# Panel_10_100_Pasive_Schematic.net
KiCad netlist of a schematic drawn in Altium Designer
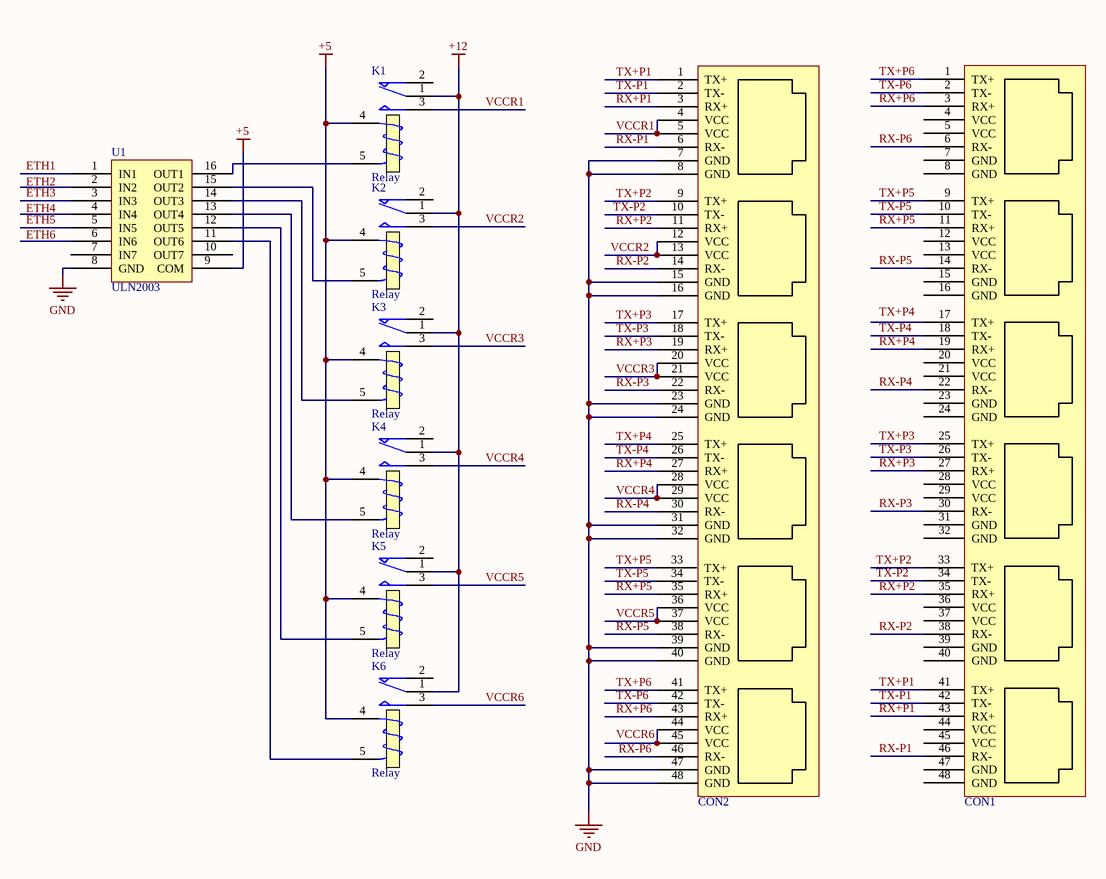
[diagram p0: Panel_10_100_Pasive_Schematic.SchDoc]

(export (version "E")
  (design (tool "Eeschema 10.0.6"))
  (components
    (comp (ref "CON1")
      (value "RJ45-w57-6")
      (footprint "RJ45-W57-6")
      (libsource (lib "Schlib1") (part "RJ45-w57-6"))
    )
    (comp (ref "CON2")
      (value "RJ45-w57-6")
      (footprint "RJ45-W57-6")
      (libsource (lib "Schlib1") (part "RJ45-w57-6"))
    )
    (comp (ref "K1")
      (value "Relay")
      (footprint "Relay 15.40x12.10x13.10")
      (description "SPDT Relay")
      (fields (field (name "DESIGNER") "Eng. Saeid Jorablo"))
      (libsource (lib "Electrovolt Lib") (part "Relay"))
    )
    (comp (ref "K2")
      (value "Relay")
      (footprint "Relay 15.40x12.10x13.10")
      (description "SPDT Relay")
      (fields (field (name "DESIGNER") "Eng. Saeid Jorablo"))
      (libsource (lib "Electrovolt Lib") (part "Relay"))
    )
    (comp (ref "K3")
      (value "Relay")
      (footprint "Relay 15.40x12.10x13.10")
      (description "SPDT Relay")
      (fields (field (name "DESIGNER") "Eng. Saeid Jorablo"))
      (libsource (lib "Electrovolt Lib") (part "Relay"))
    )
    (comp (ref "K4")
      (value "Relay")
      (footprint "Relay 15.40x12.10x13.10")
      (description "SPDT Relay")
      (fields (field (name "DESIGNER") "Eng. Saeid Jorablo"))
      (libsource (lib "Electrovolt Lib") (part "Relay"))
    )
    (comp (ref "K5")
      (value "Relay")
      (footprint "Relay 15.40x12.10x13.10")
      (description "SPDT Relay")
      (fields (field (name "DESIGNER") "Eng. Saeid Jorablo"))
      (libsource (lib "Electrovolt Lib") (part "Relay"))
    )
    (comp (ref "K6")
      (value "Relay")
      (footprint "Relay 15.40x12.10x13.10")
      (description "SPDT Relay")
      (fields (field (name "DESIGNER") "Eng. Saeid Jorablo"))
      (libsource (lib "Electrovolt Lib") (part "Relay"))
    )
    (comp (ref "U1") (value "ULN2003") (footprint "SOCI16") (libsource (lib "Schlib1") (part "ULN2003")))
  )
  (nets
    (net (code "1") (name "+5") (class "Default")
      (node (ref "K1") (pin "4") (pinfunction "T1_4") (pintype "passive"))
      (node (ref "K2") (pin "4") (pinfunction "T1_4") (pintype "passive"))
      (node (ref "K3") (pin "4") (pinfunction "T1_4") (pintype "passive"))
      (node (ref "K4") (pin "4") (pinfunction "T1_4") (pintype "passive"))
      (node (ref "K5") (pin "4") (pinfunction "T1_4") (pintype "passive"))
      (node (ref "K6") (pin "4") (pinfunction "T1_4") (pintype "passive"))
      (node (ref "U1") (pin "9") (pinfunction "COM_9") (pintype "passive"))
    )
    (net (code "2") (name "+12") (class "Default")
      (node (ref "K1") (pin "1") (pinfunction "COM_1") (pintype "passive"))
      (node (ref "K2") (pin "1") (pinfunction "COM_1") (pintype "passive"))
      (node (ref "K3") (pin "1") (pinfunction "COM_1") (pintype "passive"))
      (node (ref "K4") (pin "1") (pinfunction "COM_1") (pintype "passive"))
      (node (ref "K5") (pin "1") (pinfunction "COM_1") (pintype "passive"))
      (node (ref "K6") (pin "1") (pinfunction "COM_1") (pintype "passive"))
    )
    (net (code "3") (name "/ETH1") (class "Default")
      (node (ref "U1") (pin "1") (pinfunction "IN1_1") (pintype "passive"))
    )
    (net (code "5") (name "/ETH3") (class "Default")
      (node (ref "U1") (pin "3") (pinfunction "IN3_3") (pintype "passive"))
    )
    (net (code "7") (name "/ETH5") (class "Default")
      (node (ref "U1") (pin "5") (pinfunction "IN5_5") (pintype "passive"))
    )
    (net (code "9") (name "/RX+P1") (class "Default")
      (node (ref "CON1") (pin "43") (pinfunction "RX+_43") (pintype "passive"))
      (node (ref "CON2") (pin "3") (pinfunction "RX+_3") (pintype "passive"))
    )
    (net (code "10") (name "/RX+P2") (class "Default")
      (node (ref "CON1") (pin "35") (pinfunction "RX+_35") (pintype "passive"))
      (node (ref "CON2") (pin "11") (pinfunction "RX+_11") (pintype "passive"))
    )
    (net (code "11") (name "/RX+P3") (class "Default")
      (node (ref "CON1") (pin "27") (pinfunction "RX+_27") (pintype "passive"))
      (node (ref "CON2") (pin "19") (pinfunction "RX+_19") (pintype "passive"))
    )
    (net (code "12") (name "/RX+P4") (class "Default")
      (node (ref "CON1") (pin "19") (pinfunction "RX+_19") (pintype "passive"))
      (node (ref "CON2") (pin "27") (pinfunction "RX+_27") (pintype "passive"))
    )
    (net (code "13") (name "/RX+P5") (class "Default")
      (node (ref "CON1") (pin "11") (pinfunction "RX+_11") (pintype "passive"))
      (node (ref "CON2") (pin "35") (pinfunction "RX+_35") (pintype "passive"))
    )
    (net (code "14") (name "/RX+P6") (class "Default")
      (node (ref "CON1") (pin "3") (pinfunction "RX+_3") (pintype "passive"))
      (node (ref "CON2") (pin "43") (pinfunction "RX+_43") (pintype "passive"))
    )
    (net (code "15") (name "/RX-P1") (class "Default")
      (node (ref "CON1") (pin "46") (pinfunction "RX-_46") (pintype "passive"))
      (node (ref "CON2") (pin "6") (pinfunction "RX-_6") (pintype "passive"))
    )
    (net (code "16") (name "/RX-P2") (class "Default")
      (node (ref "CON1") (pin "38") (pinfunction "RX-_38") (pintype "passive"))
      (node (ref "CON2") (pin "14") (pinfunction "RX-_14") (pintype "passive"))
    )
    (net (code "17") (name "/RX-P3") (class "Default")
      (node (ref "CON1") (pin "30") (pinfunction "RX-_30") (pintype "passive"))
      (node (ref "CON2") (pin "22") (pinfunction "RX-_22") (pintype "passive"))
    )
    (net (code "18") (name "/RX-P4") (class "Default")
      (node (ref "CON1") (pin "22") (pinfunction "RX-_22") (pintype "passive"))
      (node (ref "CON2") (pin "30") (pinfunction "RX-_30") (pintype "passive"))
    )
    (net (code "19") (name "/RX-P5") (class "Default")
      (node (ref "CON1") (pin "14") (pinfunction "RX-_14") (pintype "passive"))
      (node (ref "CON2") (pin "38") (pinfunction "RX-_38") (pintype "passive"))
    )
    (net (code "20") (name "/RX-P6") (class "Default")
      (node (ref "CON1") (pin "6") (pinfunction "RX-_6") (pintype "passive"))
      (node (ref "CON2") (pin "46") (pinfunction "RX-_46") (pintype "passive"))
    )
    (net (code "21") (name "/TX+P1") (class "Default")
      (node (ref "CON1") (pin "41") (pinfunction "TX+_41") (pintype "passive"))
      (node (ref "CON2") (pin "1") (pinfunction "TX+_1") (pintype "passive"))
    )
    (net (code "22") (name "/TX+P2") (class "Default")
      (node (ref "CON1") (pin "33") (pinfunction "TX+_33") (pintype "passive"))
      (node (ref "CON2") (pin "9") (pinfunction "TX+_9") (pintype "passive"))
    )
    (net (code "23") (name "/TX+P3") (class "Default")
      (node (ref "CON1") (pin "25") (pinfunction "TX+_25") (pintype "passive"))
      (node (ref "CON2") (pin "17") (pinfunction "TX+_17") (pintype "passive"))
    )
    (net (code "24") (name "/TX+P4") (class "Default")
      (node (ref "CON2") (pin "25") (pinfunction "TX+_25") (pintype "passive"))
    )
    (net (code "25") (name "/TX+P5") (class "Default")
      (node (ref "CON1") (pin "9") (pinfunction "TX+_9") (pintype "passive"))
      (node (ref "CON2") (pin "33") (pinfunction "TX+_33") (pintype "passive"))
    )
    (net (code "26") (name "/TX+P6") (class "Default")
      (node (ref "CON1") (pin "1") (pinfunction "TX+_1") (pintype "passive"))
      (node (ref "CON2") (pin "41") (pinfunction "TX+_41") (pintype "passive"))
    )
    (net (code "27") (name "/TX-P1") (class "Default")
      (node (ref "CON1") (pin "42") (pinfunction "TX-_42") (pintype "passive"))
      (node (ref "CON2") (pin "2") (pinfunction "TX-_2") (pintype "passive"))
    )
    (net (code "28") (name "/TX-P2") (class "Default")
      (node (ref "CON1") (pin "34") (pinfunction "TX-_34") (pintype "passive"))
      (node (ref "CON2") (pin "10") (pinfunction "TX-_10") (pintype "passive"))
    )
    (net (code "29") (name "/TX-P3") (class "Default")
      (node (ref "CON1") (pin "26") (pinfunction "TX-_26") (pintype "passive"))
      (node (ref "CON2") (pin "18") (pinfunction "TX-_18") (pintype "passive"))
    )
    (net (code "30") (name "/TX-P4") (class "Default")
      (node (ref "CON1") (pin "18") (pinfunction "TX-_18") (pintype "passive"))
      (node (ref "CON2") (pin "26") (pinfunction "TX-_26") (pintype "passive"))
    )
    (net (code "31") (name "/TX-P5") (class "Default")
      (node (ref "CON1") (pin "10") (pinfunction "TX-_10") (pintype "passive"))
      (node (ref "CON2") (pin "34") (pinfunction "TX-_34") (pintype "passive"))
    )
    (net (code "32") (name "/TX-P6") (class "Default")
      (node (ref "CON1") (pin "2") (pinfunction "TX-_2") (pintype "passive"))
      (node (ref "CON2") (pin "42") (pinfunction "TX-_42") (pintype "passive"))
    )
    (net (code "33") (name "/VCCR1") (class "Default")
      (node (ref "CON2") (pin "4") (pinfunction "VCC_4") (pintype "passive"))
      (node (ref "CON2") (pin "5") (pinfunction "VCC_5") (pintype "passive"))
      (node (ref "K1") (pin "3") (pinfunction "NO_3") (pintype "passive"))
    )
    (net (code "34") (name "/VCCR2") (class "Default")
      (node (ref "CON2") (pin "12") (pinfunction "VCC_12") (pintype "passive"))
      (node (ref "CON2") (pin "13") (pinfunction "VCC_13") (pintype "passive"))
      (node (ref "K2") (pin "3") (pinfunction "NO_3") (pintype "passive"))
    )
    (net (code "35") (name "/VCCR3") (class "Default")
      (node (ref "CON2") (pin "20") (pinfunction "VCC_20") (pintype "passive"))
      (node (ref "CON2") (pin "21") (pinfunction "VCC_21") (pintype "passive"))
      (node (ref "K3") (pin "3") (pinfunction "NO_3") (pintype "passive"))
    )
    (net (code "36") (name "/VCCR4") (class "Default")
      (node (ref "CON2") (pin "28") (pinfunction "VCC_28") (pintype "passive"))
      (node (ref "CON2") (pin "29") (pinfunction "VCC_29") (pintype "passive"))
      (node (ref "K4") (pin "3") (pinfunction "NO_3") (pintype "passive"))
    )
    (net (code "37") (name "/VCCR5") (class "Default")
      (node (ref "CON2") (pin "36") (pinfunction "VCC_36") (pintype "passive"))
      (node (ref "CON2") (pin "37") (pinfunction "VCC_37") (pintype "passive"))
      (node (ref "K5") (pin "3") (pinfunction "NO_3") (pintype "passive"))
    )
    (net (code "38") (name "/VCCR6") (class "Default")
      (node (ref "K6") (pin "3") (pinfunction "NO_3") (pintype "passive"))
    )
    (net (code "39") (name "GND") (class "Default")
      (node (ref "CON2") (pin "15") (pinfunction "GND_15") (pintype "passive"))
      (node (ref "CON2") (pin "16") (pinfunction "GND_16") (pintype "passive"))
      (node (ref "CON2") (pin "23") (pinfunction "GND_23") (pintype "passive"))
      (node (ref "CON2") (pin "24") (pinfunction "GND_24") (pintype "passive"))
      (node (ref "CON2") (pin "31") (pinfunction "GND_31") (pintype "passive"))
      (node (ref "CON2") (pin "32") (pinfunction "GND_32") (pintype "passive"))
      (node (ref "CON2") (pin "39") (pinfunction "GND_39") (pintype "passive"))
      (node (ref "CON2") (pin "40") (pinfunction "GND_40") (pintype "passive"))
      (node (ref "CON2") (pin "47") (pinfunction "GND_47") (pintype "passive"))
      (node (ref "CON2") (pin "48") (pinfunction "GND_48") (pintype "passive"))
      (node (ref "CON2") (pin "7") (pinfunction "GND_7") (pintype "passive"))
      (node (ref "CON2") (pin "8") (pinfunction "GND_8") (pintype "passive"))
      (node (ref "U1") (pin "8") (pinfunction "GND_8") (pintype "passive"))
    )
    (net (code "40") (name "Net-(CON2-VCC-Pad44)") (class "Default")
      (node (ref "CON2") (pin "44") (pinfunction "VCC_44") (pintype "passive"))
      (node (ref "CON2") (pin "45") (pinfunction "VCC_45") (pintype "passive"))
    )
    (net (code "41") (name "Net-(K1-T2)") (class "Default")
      (node (ref "K1") (pin "5") (pinfunction "T2_5") (pintype "passive"))
      (node (ref "U1") (pin "16") (pinfunction "OUT1_16") (pintype "passive"))
    )
    (net (code "42") (name "Net-(K2-T2)") (class "Default")
      (node (ref "K2") (pin "5") (pinfunction "T2_5") (pintype "passive"))
      (node (ref "U1") (pin "15") (pinfunction "OUT2_15") (pintype "passive"))
    )
    (net (code "43") (name "Net-(K3-T2)") (class "Default")
      (node (ref "K3") (pin "5") (pinfunction "T2_5") (pintype "passive"))
      (node (ref "U1") (pin "14") (pinfunction "OUT3_14") (pintype "passive"))
    )
    (net (code "44") (name "Net-(K4-T2)") (class "Default")
      (node (ref "K4") (pin "5") (pinfunction "T2_5") (pintype "passive"))
      (node (ref "U1") (pin "13") (pinfunction "OUT4_13") (pintype "passive"))
    )
    (net (code "45") (name "Net-(K5-T2)") (class "Default")
      (node (ref "K5") (pin "5") (pinfunction "T2_5") (pintype "passive"))
      (node (ref "U1") (pin "12") (pinfunction "OUT5_12") (pintype "passive"))
    )
    (net (code "46") (name "Net-(K6-T2)") (class "Default")
      (node (ref "K6") (pin "5") (pinfunction "T2_5") (pintype "passive"))
      (node (ref "U1") (pin "11") (pinfunction "OUT6_11") (pintype "passive"))
    )
    (net (code "47") (name "unconnected-(CON1-GND-Pad7)") (class "Default")
      (node (ref "CON1") (pin "7") (pinfunction "GND_7") (pintype "passive"))
    )
    (net (code "48") (name "unconnected-(CON1-GND-Pad8)") (class "Default")
      (node (ref "CON1") (pin "8") (pinfunction "GND_8") (pintype "passive"))
    )
    (net (code "49") (name "unconnected-(CON1-GND-Pad15)") (class "Default")
      (node (ref "CON1") (pin "15") (pinfunction "GND_15") (pintype "passive"))
    )
    (net (code "50") (name "unconnected-(CON1-GND-Pad16)") (class "Default")
      (node (ref "CON1") (pin "16") (pinfunction "GND_16") (pintype "passive"))
    )
    (net (code "51") (name "unconnected-(CON1-GND-Pad23)") (class "Default")
      (node (ref "CON1") (pin "23") (pinfunction "GND_23") (pintype "passive"))
    )
    (net (code "52") (name "unconnected-(CON1-GND-Pad24)") (class "Default")
      (node (ref "CON1") (pin "24") (pinfunction "GND_24") (pintype "passive"))
    )
    (net (code "53") (name "unconnected-(CON1-GND-Pad31)") (class "Default")
      (node (ref "CON1") (pin "31") (pinfunction "GND_31") (pintype "passive"))
    )
    (net (code "54") (name "unconnected-(CON1-GND-Pad32)") (class "Default")
      (node (ref "CON1") (pin "32") (pinfunction "GND_32") (pintype "passive"))
    )
    (net (code "55") (name "unconnected-(CON1-GND-Pad39)") (class "Default")
      (node (ref "CON1") (pin "39") (pinfunction "GND_39") (pintype "passive"))
    )
    (net (code "56") (name "unconnected-(CON1-GND-Pad40)") (class "Default")
      (node (ref "CON1") (pin "40") (pinfunction "GND_40") (pintype "passive"))
    )
    (net (code "57") (name "unconnected-(CON1-GND-Pad47)") (class "Default")
      (node (ref "CON1") (pin "47") (pinfunction "GND_47") (pintype "passive"))
    )
    (net (code "58") (name "unconnected-(CON1-GND-Pad48)") (class "Default")
      (node (ref "CON1") (pin "48") (pinfunction "GND_48") (pintype "passive"))
    )
    (net (code "59") (name "unconnected-(CON1-TX+-Pad17)") (class "Default")
      (node (ref "CON1") (pin "17") (pinfunction "TX+_17") (pintype "passive"))
    )
    (net (code "60") (name "unconnected-(CON1-VCC-Pad4)") (class "Default")
      (node (ref "CON1") (pin "4") (pinfunction "VCC_4") (pintype "passive"))
    )
    (net (code "61") (name "unconnected-(CON1-VCC-Pad5)") (class "Default")
      (node (ref "CON1") (pin "5") (pinfunction "VCC_5") (pintype "passive"))
    )
    (net (code "62") (name "unconnected-(CON1-VCC-Pad12)") (class "Default")
      (node (ref "CON1") (pin "12") (pinfunction "VCC_12") (pintype "passive"))
    )
    (net (code "63") (name "unconnected-(CON1-VCC-Pad13)") (class "Default")
      (node (ref "CON1") (pin "13") (pinfunction "VCC_13") (pintype "passive"))
    )
    (net (code "64") (name "unconnected-(CON1-VCC-Pad20)") (class "Default")
      (node (ref "CON1") (pin "20") (pinfunction "VCC_20") (pintype "passive"))
    )
    (net (code "65") (name "unconnected-(CON1-VCC-Pad21)") (class "Default")
      (node (ref "CON1") (pin "21") (pinfunction "VCC_21") (pintype "passive"))
    )
    (net (code "66") (name "unconnected-(CON1-VCC-Pad28)") (class "Default")
      (node (ref "CON1") (pin "28") (pinfunction "VCC_28") (pintype "passive"))
    )
    (net (code "67") (name "unconnected-(CON1-VCC-Pad29)") (class "Default")
      (node (ref "CON1") (pin "29") (pinfunction "VCC_29") (pintype "passive"))
    )
    (net (code "68") (name "unconnected-(CON1-VCC-Pad36)") (class "Default")
      (node (ref "CON1") (pin "36") (pinfunction "VCC_36") (pintype "passive"))
    )
    (net (code "69") (name "unconnected-(CON1-VCC-Pad37)") (class "Default")
      (node (ref "CON1") (pin "37") (pinfunction "VCC_37") (pintype "passive"))
    )
    (net (code "70") (name "unconnected-(CON1-VCC-Pad44)") (class "Default")
      (node (ref "CON1") (pin "44") (pinfunction "VCC_44") (pintype "passive"))
    )
    (net (code "71") (name "unconnected-(CON1-VCC-Pad45)") (class "Default")
      (node (ref "CON1") (pin "45") (pinfunction "VCC_45") (pintype "passive"))
    )
    (net (code "72") (name "unconnected-(K1-NC-Pad2)") (class "Default")
      (node (ref "K1") (pin "2") (pinfunction "NC_2") (pintype "passive"))
    )
    (net (code "73") (name "unconnected-(K2-NC-Pad2)") (class "Default")
      (node (ref "K2") (pin "2") (pinfunction "NC_2") (pintype "passive"))
    )
    (net (code "74") (name "unconnected-(K3-NC-Pad2)") (class "Default")
      (node (ref "K3") (pin "2") (pinfunction "NC_2") (pintype "passive"))
    )
    (net (code "75") (name "unconnected-(K4-NC-Pad2)") (class "Default")
      (node (ref "K4") (pin "2") (pinfunction "NC_2") (pintype "passive"))
    )
    (net (code "76") (name "unconnected-(K5-NC-Pad2)") (class "Default")
      (node (ref "K5") (pin "2") (pinfunction "NC_2") (pintype "passive"))
    )
    (net (code "77") (name "unconnected-(K6-NC-Pad2)") (class "Default")
      (node (ref "K6") (pin "2") (pinfunction "NC_2") (pintype "passive"))
    )
    (net (code "78") (name "unconnected-(U1-IN2-Pad2)") (class "Default")
      (node (ref "U1") (pin "2") (pinfunction "IN2_2") (pintype "passive"))
    )
    (net (code "79") (name "unconnected-(U1-IN4-Pad4)") (class "Default")
      (node (ref "U1") (pin "4") (pinfunction "IN4_4") (pintype "passive"))
    )
    (net (code "80") (name "unconnected-(U1-IN6-Pad6)") (class "Default")
      (node (ref "U1") (pin "6") (pinfunction "IN6_6") (pintype "passive"))
    )
    (net (code "81") (name "unconnected-(U1-IN7-Pad7)") (class "Default")
      (node (ref "U1") (pin "7") (pinfunction "IN7_7") (pintype "passive"))
    )
    (net (code "82") (name "unconnected-(U1-OUT7-Pad10)") (class "Default")
      (node (ref "U1") (pin "10") (pinfunction "OUT7_10") (pintype "passive"))
    )
  )
)
